# WIZ850io_SCH_V100.net
KiCad netlist of a schematic drawn in Altium Designer
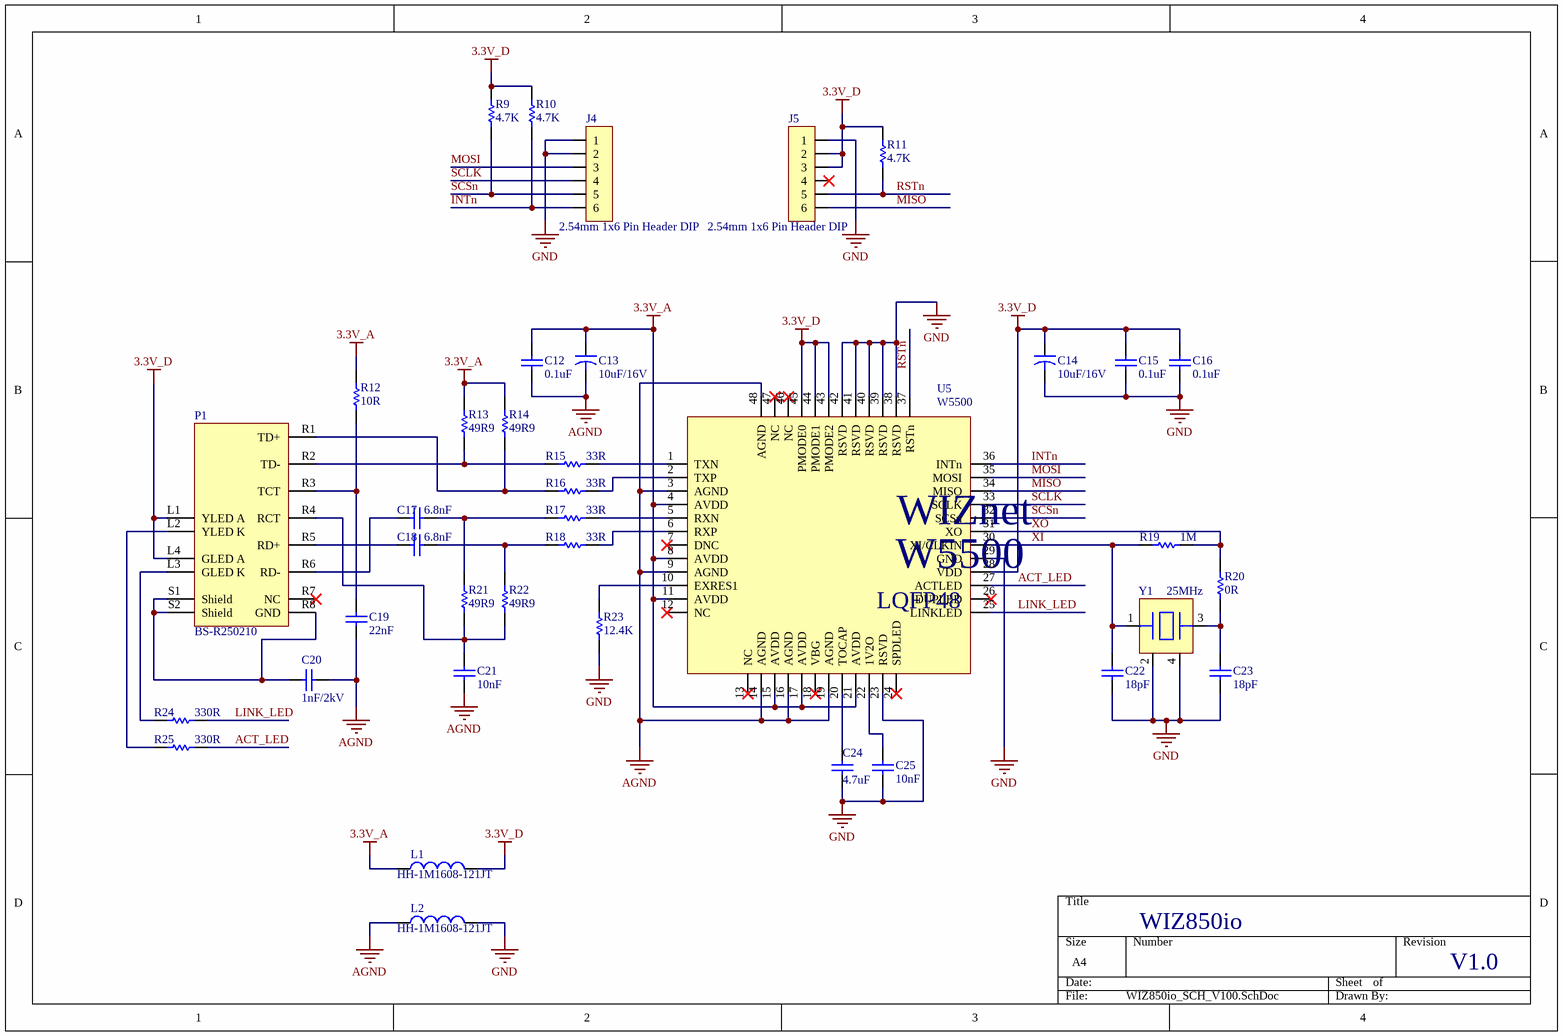
[diagram p0: WIZ850io_SCH_V100.SchDoc]

(export (version "E")
  (design (tool "Eeschema 10.0.6"))
  (components
    (comp (ref "C12")
      (value "0.1uF")
      (footprint "*CAPC1608X90N")
      (description "CAP CER 0.1UF 25V X7R 0603")
      (fields
        (field (name "MANUFACTURER") "Kyocera AVX")
        (field (name "MANUFACTURER PART NUMBER") "06033C104JAT2A")
      )
      (libsource (lib "Scott_lib") (part "CAP-0402"))
    )
    (comp (ref "C13")
      (value "10uF/16V")
      (footprint "10uF 16V")
      (description "Cap Ceramic 10uF 16V X5R 20% SMD 0603 85°C Paper T/R")
      (fields
        (field (name "MANUFACTURER") "Taiyo Yuden")
        (field (name "MANUFACTURER PART NUMBER") "EMK107BBJ106MA-T")
      )
      (libsource (lib "Scott_lib") (part "CAP-A Size"))
    )
    (comp (ref "C14")
      (value "10uF/16V")
      (footprint "10uF 16V")
      (description "Cap Ceramic 10uF 16V X5R 20% SMD 0603 85°C Paper T/R")
      (fields
        (field (name "MANUFACTURER") "Taiyo Yuden")
        (field (name "MANUFACTURER PART NUMBER") "EMK107BBJ106MA-T")
      )
      (libsource (lib "Scott_lib") (part "CAP-A Size"))
    )
    (comp (ref "C15")
      (value "0.1uF")
      (footprint "*CAPC1608X90N")
      (description "CAP CER 0.1UF 25V X7R 0603")
      (fields
        (field (name "MANUFACTURER") "Kyocera AVX")
        (field (name "MANUFACTURER PART NUMBER") "06033C104JAT2A")
      )
      (libsource (lib "Scott_lib") (part "CAP-0402"))
    )
    (comp (ref "C16")
      (value "0.1uF")
      (footprint "*CAPC1608X90N")
      (description "CAP CER 0.1UF 25V X7R 0603")
      (fields
        (field (name "MANUFACTURER") "Kyocera AVX")
        (field (name "MANUFACTURER PART NUMBER") "06033C104JAT2A")
      )
      (libsource (lib "Scott_lib") (part "CAP-0402"))
    )
    (comp (ref "C17")
      (value "6.8nF")
      (footprint "6.8nF")
      (fields
        (field (name "MANUFACTURER") "Kyocera AVX")
        (field (name "MANUFACTURER PART NUMBER") "06031C682KAT2A")
        (field (name "TOLERANCE") "10%")
      )
      (libsource (lib "Scott_lib") (part "CAP-0402"))
    )
    (comp (ref "C18")
      (value "6.8nF")
      (footprint "6.8nF")
      (fields
        (field (name "MANUFACTURER") "Kyocera AVX")
        (field (name "MANUFACTURER PART NUMBER") "06031C682KAT2A")
        (field (name "TOLERANCE") "10%")
      )
      (libsource (lib "Scott_lib") (part "CAP-0402"))
    )
    (comp (ref "C19")
      (value "22nF")
      (footprint "22nF")
      (description "Cap Ceramic 0.022uF 25V X7R 10% SMD 0603 125°C Paper T/R")
      (fields
        (field (name "MANUFACTURER") "Kyocera AVX")
        (field (name "MANUFACTURER PART NUMBER") "06033C223KAT2A")
      )
      (libsource (lib "Scott_lib") (part "CAP-0402"))
    )
    (comp (ref "C20")
      (value "1nF/2kV")
      (footprint "1nF/2kV")
      (description "Cap Ceramic 0.001uF 50V X7R 10% SMD 0603 125C Paper T/R")
      (fields
        (field (name "MANUFACTURER") "Kyocera AVX")
        (field (name "MANUFACTURER PART NUMBER") "06035C102KAT2A")
      )
      (libsource (lib "Scott_lib") (part "CAP-1808"))
    )
    (comp (ref "C21")
      (value "10nF")
      (footprint "10nF")
      (description "0603 10nF 50 V ±10 % Tolerance X7R Surface Mount Multilayer Ceramic Capacitor")
      (fields
        (field (name "MANUFACTURER") "Kyocera AVX")
        (field (name "MANUFACTURER PART NUMBER") "06035C103KAT2A")
      )
      (libsource (lib "Scott_lib") (part "CAP-0402"))
    )
    (comp (ref "C22")
      (value "18pF")
      (footprint "18pF")
      (fields
        (field (name "MANUFACTURER") "Kyocera AVX")
        (field (name "MANUFACTURER PART NUMBER") "06031A180JAT2A")
        (field (name "TOLERANCE") "5%")
      )
      (libsource (lib "Scott_lib") (part "CAP-0402"))
    )
    (comp (ref "C23")
      (value "18pF")
      (footprint "18pF")
      (fields
        (field (name "MANUFACTURER") "Kyocera AVX")
        (field (name "MANUFACTURER PART NUMBER") "06031A180JAT2A")
        (field (name "TOLERANCE") "5%")
      )
      (libsource (lib "Scott_lib") (part "CAP-0402"))
    )
    (comp (ref "C24")
      (value "4.7uF")
      (footprint "4.7 uF")
      (description "Ceramic CAP 0402(1005)")
      (libsource (lib "Scott_lib") (part "CAP-0402"))
    )
    (comp (ref "C25")
      (value "10nF")
      (footprint "10nF")
      (description "0603 10nF 50 V ±10 % Tolerance X7R Surface Mount Multilayer Ceramic Capacitor")
      (fields
        (field (name "MANUFACTURER") "Kyocera AVX")
        (field (name "MANUFACTURER PART NUMBER") "06035C103KAT2A")
      )
      (libsource (lib "Scott_lib") (part "CAP-0805"))
    )
    (comp (ref "J4")
      (value "2.54mm 1x6 Pin Header DIP")
      (footprint "IDC-1X6")
      (libsource (lib "") (part "2.54mm 1x6 Pin Header DIP_1"))
    )
    (comp (ref "J5")
      (value "2.54mm 1x6 Pin Header DIP")
      (footprint "IDC-1X6")
      (libsource (lib "Scott_lib") (part "2.54mm 1x6 Pin Header DIP"))
    )
    (comp (ref "L1")
      (value "HH-1M1608-121JT")
      (footprint "IND-0603")
      (description "Inductor 0603(1608)")
      (libsource (lib "Scott_lib") (part "IND-0603"))
    )
    (comp (ref "L2")
      (value "HH-1M1608-121JT")
      (footprint "IND-0603")
      (description "Inductor 0603(1608)")
      (libsource (lib "Scott_lib") (part "IND-0603"))
    )
    (comp (ref "P1")
      (value "BS-R250210")
      (footprint "BS-R250210")
      (libsource (lib "Scott_lib") (part "BS-R250210"))
    )
    (comp (ref "R9")
      (value "4.7K")
      (footprint "4.7k OHM R")
      (description "SMD Resistor, Thick film 4.7 kOhm,  ±  1 %, 0603, CRCW06034K70FKEA, Vishay")
      (fields
        (field (name "MANUFACTURER") "Vishay Dale")
        (field (name "MANUFACTURER PART NUMBER") "CRA06S0434K70JTA")
      )
      (libsource (lib "Scott_lib") (part "RES-0402"))
    )
    (comp (ref "R10")
      (value "4.7K")
      (footprint "4.7k OHM R")
      (description "SMD Resistor, Thick film 4.7 kOhm,  ±  1 %, 0603, CRCW06034K70FKEA, Vishay")
      (fields
        (field (name "MANUFACTURER") "Vishay Dale")
        (field (name "MANUFACTURER PART NUMBER") "CRA06S0434K70JTA")
      )
      (libsource (lib "Scott_lib") (part "RES-0402"))
    )
    (comp (ref "R11")
      (value "4.7K")
      (footprint "4.7k OHM R")
      (description "SMD Resistor, Thick film 4.7 kOhm,  ±  1 %, 0603, CRCW06034K70FKEA, Vishay")
      (fields
        (field (name "MANUFACTURER") "Vishay")
        (field (name "MANUFACTURER PART NUMBER") "CRCW12064K70FKEA")
      )
      (libsource (lib "Scott_lib") (part "RES-0402"))
    )
    (comp (ref "R12")
      (value "10R")
      (footprint "10OHM R")
      (description "Res Thick Film 0603 10 Ohm 1% 1/10W ±100ppm/°C Molded SMD Paper T/R")
      (fields
        (field (name "MANUFACTURER") "Vishay Dale")
        (field (name "MANUFACTURER PART NUMBER") "CRA06S04310R0JTA")
      )
      (libsource (lib "Scott_lib") (part "RES-0402"))
    )
    (comp (ref "R13")
      (value "49R9")
      (footprint "49R9 OHM")
      (description "VISHAY - TNPW060349R9BEEA. - TNPW0603 49R9 0.1% T-9 ET1 E3 ROHS COMPLIANT: YES")
      (fields
        (field (name "MANUFACTURER") "Vishay Dale")
        (field (name "MANUFACTURER PART NUMBER") "CRA06S04349R9FTA")
      )
      (libsource (lib "Scott_lib") (part "RES-0402"))
    )
    (comp (ref "R14")
      (value "49R9")
      (footprint "49R9 OHM")
      (description "VISHAY - TNPW060349R9BEEA. - TNPW0603 49R9 0.1% T-9 ET1 E3 ROHS COMPLIANT: YES")
      (fields
        (field (name "MANUFACTURER") "Vishay Dale")
        (field (name "MANUFACTURER PART NUMBER") "CRA06S04349R9FTA")
      )
      (libsource (lib "Scott_lib") (part "RES-0402"))
    )
    (comp (ref "R15")
      (value "33R")
      (footprint "33OHM R")
      (fields
        (field (name "MANUFACTURER") "Vishay Dale")
        (field (name "MANUFACTURER PART NUMBER") "CRA06S04333R0JTA")
        (field (name "TOLERANCE") "5%")
      )
      (libsource (lib "Scott_lib") (part "RES-0402"))
    )
    (comp (ref "R16")
      (value "33R")
      (footprint "33OHM R")
      (fields
        (field (name "MANUFACTURER") "Vishay Dale")
        (field (name "MANUFACTURER PART NUMBER") "CRA06S04333R0JTA")
        (field (name "TOLERANCE") "5%")
      )
      (libsource (lib "Scott_lib") (part "RES-0402"))
    )
    (comp (ref "R17")
      (value "33R")
      (footprint "33OHM R")
      (fields
        (field (name "MANUFACTURER") "Vishay Dale")
        (field (name "MANUFACTURER PART NUMBER") "CRA06S04333R0JTA")
        (field (name "TOLERANCE") "5%")
      )
      (libsource (lib "Scott_lib") (part "RES-0402"))
    )
    (comp (ref "R18")
      (value "33R")
      (footprint "33OHM R")
      (fields
        (field (name "MANUFACTURER") "Vishay Dale")
        (field (name "MANUFACTURER PART NUMBER") "CRA06S04333R0JTA")
        (field (name "TOLERANCE") "5%")
      )
      (libsource (lib "Scott_lib") (part "RES-0402"))
    )
    (comp (ref "R19")
      (value "1M")
      (footprint "1M OHM R")
      (description "Thick Film Chip Resistor")
      (fields
        (field (name "MANUFACTURER") "Vishay Dale")
        (field (name "MANUFACTURER PART NUMBER") "CRA06S0431M00JTA")
      )
      (libsource (lib "Scott_lib") (part "RES-0402"))
    )
    (comp (ref "R20")
      (value "0R")
      (footprint "0 OHM R")
      (description "Resistor SMD 0 Ohm 0603 PU=5000 ST, CRCW06030000Z0EA, Vishay")
      (fields
        (field (name "MANUFACTURER") "Vishay")
        (field (name "MANUFACTURER PART NUMBER") "CRCW0603-0000Z0EA")
      )
      (libsource (lib "Scott_lib") (part "RES-0402"))
    )
    (comp (ref "R21")
      (value "49R9")
      (footprint "49R9 OHM")
      (description "VISHAY - TNPW060349R9BEEA. - TNPW0603 49R9 0.1% T-9 ET1 E3 ROHS COMPLIANT: YES")
      (fields
        (field (name "MANUFACTURER") "Vishay Dale")
        (field (name "MANUFACTURER PART NUMBER") "CRA06S04349R9FTA")
      )
      (libsource (lib "Scott_lib") (part "RES-0402"))
    )
    (comp (ref "R22")
      (value "49R9")
      (footprint "49R9 OHM")
      (description "VISHAY - TNPW060349R9BEEA. - TNPW0603 49R9 0.1% T-9 ET1 E3 ROHS COMPLIANT: YES")
      (fields
        (field (name "MANUFACTURER") "Vishay Dale")
        (field (name "MANUFACTURER PART NUMBER") "CRA06S04349R9FTA")
      )
      (libsource (lib "Scott_lib") (part "RES-0402"))
    )
    (comp (ref "R23")
      (value "12.4K")
      (footprint "12.4k OHM R")
      (description "Res Thick Film 0603 12.4K Ohm 1% 1/10W ±100ppm/°C Molded SMD SMD Paper T/R")
      (fields
        (field (name "MANUFACTURER") "Vishay")
        (field (name "MANUFACTURER PART NUMBER") "CRCW0603-12K4FKEA")
      )
      (libsource (lib "Scott_lib") (part "RES-0402"))
    )
    (comp (ref "R24")
      (value "330R")
      (footprint "ahhhh")
      (description "Res Thick Film 0603 330 Ohm 1% 0.1W(1/10W) +/-100ppm/ßC Pad SMD Automotive T/R")
      (fields
        (field (name "MANUFACTURER") "Vishay Dale")
        (field (name "MANUFACTURER PART NUMBER") "CRA06S043330RJTA")
      )
      (libsource (lib "Scott_lib") (part "RES-0402"))
    )
    (comp (ref "R25")
      (value "330R")
      (footprint "ahhhh")
      (description "Res Thick Film 0603 330 Ohm 1% 0.1W(1/10W) +/-100ppm/ßC Pad SMD Automotive T/R")
      (fields
        (field (name "MANUFACTURER") "Vishay Dale")
        (field (name "MANUFACTURER PART NUMBER") "CRA06S043330RJTA")
      )
      (libsource (lib "Scott_lib") (part "RES-0402"))
    )
    (comp (ref "U5")
      (value "W5500")
      (footprint "WIZnet W5500")
      (description "Ethernet CTLR Single Chip 10Mbps/100Mbps 3.3V 48-Pin LQFP Reel")
      (fields (field (name "MANUFACTURER") "WIZnet"))
      (libsource (lib "WIZnet Open-source Hardware Library V1.0") (part "W5500"))
    )
    (comp (ref "Y1")
      (value "25MHz")
      (footprint "OSC-82J0626")
      (description "X-tal 25MHz,3.2x2.5 SMD, CL=18pF")
      (libsource (lib "Scott_lib") (part "OSC-82J0626-25MHz"))
    )
  )
  (nets
    (net (code "1") (name "/ACT_LED") (class "Default")
      (node (ref "R25") (pin "2") (pinfunction "2_2") (pintype "passive"))
      (node (ref "U5") (pin "27") (pinfunction "ACTLED_27") (pintype "passive"))
    )
    (net (code "2") (name "/INTn") (class "Default")
      (node (ref "J4") (pin "6") (pinfunction "6_6") (pintype "passive"))
      (node (ref "R10") (pin "1") (pinfunction "1_1") (pintype "passive"))
      (node (ref "U5") (pin "36") (pinfunction "INTn_36") (pintype "passive"))
    )
    (net (code "3") (name "/LINK_LED") (class "Default")
      (node (ref "R24") (pin "2") (pinfunction "2_2") (pintype "passive"))
      (node (ref "U5") (pin "25") (pinfunction "LINKLED_25") (pintype "passive"))
    )
    (net (code "4") (name "/MISO") (class "Default")
      (node (ref "J5") (pin "6") (pinfunction "6_6") (pintype "passive"))
      (node (ref "U5") (pin "34") (pinfunction "MISO_34") (pintype "passive"))
    )
    (net (code "5") (name "/MOSI") (class "Default")
      (node (ref "J4") (pin "3") (pinfunction "3_3") (pintype "passive"))
      (node (ref "U5") (pin "35") (pinfunction "MOSI_35") (pintype "passive"))
    )
    (net (code "6") (name "/RSTn") (class "Default")
      (node (ref "J5") (pin "5") (pinfunction "5_5") (pintype "passive"))
      (node (ref "R11") (pin "1") (pinfunction "1_1") (pintype "passive"))
      (node (ref "U5") (pin "37") (pinfunction "RSTn_37") (pintype "passive"))
    )
    (net (code "7") (name "/SCLK") (class "Default")
      (node (ref "J4") (pin "4") (pinfunction "4_4") (pintype "passive"))
      (node (ref "U5") (pin "33") (pinfunction "SCLK_33") (pintype "passive"))
    )
    (net (code "8") (name "/SCSn") (class "Default")
      (node (ref "J4") (pin "5") (pinfunction "5_5") (pintype "passive"))
      (node (ref "R9") (pin "1") (pinfunction "1_1") (pintype "passive"))
      (node (ref "U5") (pin "32") (pinfunction "SCSn_32") (pintype "passive"))
    )
    (net (code "9") (name "/XI") (class "Default")
      (node (ref "C22") (pin "2") (pinfunction "2_2") (pintype "passive"))
      (node (ref "R19") (pin "1") (pinfunction "1_1") (pintype "passive"))
      (node (ref "U5") (pin "30") (pinfunction "XI/CLKIN_30") (pintype "passive"))
      (node (ref "Y1") (pin "1") (pinfunction "1_1") (pintype "passive"))
    )
    (net (code "10") (name "/XO") (class "Default")
      (node (ref "R19") (pin "2") (pinfunction "2_2") (pintype "passive"))
      (node (ref "R20") (pin "2") (pinfunction "2_2") (pintype "passive"))
      (node (ref "U5") (pin "31") (pinfunction "XO_31") (pintype "passive"))
    )
    (net (code "11") (name "3.3V_A") (class "Default")
      (node (ref "C12") (pin "2") (pinfunction "2_2") (pintype "passive"))
      (node (ref "C13") (pin "1") (pinfunction "1_1") (pintype "passive"))
      (node (ref "L1") (pin "1") (pinfunction "1_1") (pintype "passive"))
      (node (ref "R12") (pin "2") (pinfunction "2_2") (pintype "passive"))
      (node (ref "R13") (pin "2") (pinfunction "2_2") (pintype "passive"))
      (node (ref "R14") (pin "2") (pinfunction "2_2") (pintype "passive"))
      (node (ref "U5") (pin "11") (pinfunction "AVDD_11") (pintype "passive"))
      (node (ref "U5") (pin "15") (pinfunction "AVDD_15") (pintype "passive"))
      (node (ref "U5") (pin "17") (pinfunction "AVDD_17") (pintype "passive"))
      (node (ref "U5") (pin "21") (pinfunction "AVDD_21") (pintype "passive"))
      (node (ref "U5") (pin "4") (pinfunction "AVDD_4") (pintype "passive"))
      (node (ref "U5") (pin "8") (pinfunction "AVDD_8") (pintype "passive"))
    )
    (net (code "12") (name "3.3V_D") (class "Default")
      (node (ref "C14") (pin "1") (pinfunction "1_1") (pintype "passive"))
      (node (ref "C15") (pin "2") (pinfunction "2_2") (pintype "passive"))
      (node (ref "C16") (pin "2") (pinfunction "2_2") (pintype "passive"))
      (node (ref "J5") (pin "2") (pinfunction "2_2") (pintype "passive"))
      (node (ref "J5") (pin "3") (pinfunction "3_3") (pintype "passive"))
      (node (ref "L1") (pin "2") (pinfunction "2_2") (pintype "passive"))
      (node (ref "P1") (pin "L1") (pinfunction "YLED_A_L1") (pintype "passive"))
      (node (ref "P1") (pin "L4") (pinfunction "GLED_A_L4") (pintype "passive"))
      (node (ref "R10") (pin "2") (pinfunction "2_2") (pintype "passive"))
      (node (ref "R11") (pin "2") (pinfunction "2_2") (pintype "passive"))
      (node (ref "R9") (pin "2") (pinfunction "2_2") (pintype "passive"))
      (node (ref "U5") (pin "28") (pinfunction "VDD_28") (pintype "passive"))
      (node (ref "U5") (pin "43") (pinfunction "PMODE2_43") (pintype "passive"))
      (node (ref "U5") (pin "44") (pinfunction "PMODE1_44") (pintype "passive"))
      (node (ref "U5") (pin "45") (pinfunction "PMODE0_45") (pintype "passive"))
    )
    (net (code "13") (name "AGND") (class "Default")
      (node (ref "C12") (pin "1") (pinfunction "1_1") (pintype "passive"))
      (node (ref "C13") (pin "2") (pinfunction "2_2") (pintype "passive"))
      (node (ref "C19") (pin "1") (pinfunction "1_1") (pintype "passive"))
      (node (ref "C20") (pin "1") (pinfunction "1_1") (pintype "passive"))
      (node (ref "C21") (pin "1") (pinfunction "1_1") (pintype "passive"))
      (node (ref "L2") (pin "1") (pinfunction "1_1") (pintype "passive"))
      (node (ref "U5") (pin "14") (pinfunction "AGND_14") (pintype "passive"))
      (node (ref "U5") (pin "16") (pinfunction "AGND_16") (pintype "passive"))
      (node (ref "U5") (pin "19") (pinfunction "AGND_19") (pintype "passive"))
      (node (ref "U5") (pin "3") (pinfunction "AGND_3") (pintype "passive"))
      (node (ref "U5") (pin "48") (pinfunction "AGND_48") (pintype "passive"))
      (node (ref "U5") (pin "9") (pinfunction "AGND_9") (pintype "passive"))
    )
    (net (code "14") (name "GND") (class "Default")
      (node (ref "C14") (pin "2") (pinfunction "2_2") (pintype "passive"))
      (node (ref "C15") (pin "1") (pinfunction "1_1") (pintype "passive"))
      (node (ref "C16") (pin "1") (pinfunction "1_1") (pintype "passive"))
      (node (ref "C22") (pin "1") (pinfunction "1_1") (pintype "passive"))
      (node (ref "C23") (pin "1") (pinfunction "1_1") (pintype "passive"))
      (node (ref "C24") (pin "1") (pinfunction "1_1") (pintype "passive"))
      (node (ref "C25") (pin "1") (pinfunction "1_1") (pintype "passive"))
      (node (ref "J4") (pin "1") (pinfunction "1_1") (pintype "passive"))
      (node (ref "J4") (pin "2") (pinfunction "2_2") (pintype "passive"))
      (node (ref "J5") (pin "1") (pinfunction "1_1") (pintype "passive"))
      (node (ref "L2") (pin "2") (pinfunction "2_2") (pintype "passive"))
      (node (ref "R23") (pin "1") (pinfunction "1_1") (pintype "passive"))
      (node (ref "U5") (pin "23") (pinfunction "RSVD_23") (pintype "passive"))
      (node (ref "U5") (pin "29") (pinfunction "GND_29") (pintype "passive"))
      (node (ref "U5") (pin "38") (pinfunction "RSVD_38") (pintype "passive"))
      (node (ref "U5") (pin "39") (pinfunction "RSVD_39") (pintype "passive"))
      (node (ref "U5") (pin "40") (pinfunction "RSVD_40") (pintype "passive"))
      (node (ref "U5") (pin "41") (pinfunction "RSVD_41") (pintype "passive"))
      (node (ref "U5") (pin "42") (pinfunction "RSVD_42") (pintype "passive"))
      (node (ref "Y1") (pin "2") (pinfunction "2_2") (pintype "passive"))
      (node (ref "Y1") (pin "4") (pinfunction "4_4") (pintype "passive"))
    )
    (net (code "15") (name "Net-(C17-Pad2)") (class "Default")
      (node (ref "C17") (pin "2") (pinfunction "2_2") (pintype "passive"))
      (node (ref "R17") (pin "1") (pinfunction "1_1") (pintype "passive"))
      (node (ref "R21") (pin "2") (pinfunction "2_2") (pintype "passive"))
    )
    (net (code "16") (name "Net-(C18-Pad2)") (class "Default")
      (node (ref "C18") (pin "2") (pinfunction "2_2") (pintype "passive"))
      (node (ref "R18") (pin "1") (pinfunction "1_1") (pintype "passive"))
      (node (ref "R22") (pin "2") (pinfunction "2_2") (pintype "passive"))
    )
    (net (code "17") (name "Net-(C23-Pad2)") (class "Default")
      (node (ref "C23") (pin "2") (pinfunction "2_2") (pintype "passive"))
      (node (ref "R20") (pin "1") (pinfunction "1_1") (pintype "passive"))
      (node (ref "Y1") (pin "3") (pinfunction "3_3") (pintype "passive"))
    )
    (net (code "18") (name "Net-(P1-GLED_K)") (class "Default")
      (node (ref "P1") (pin "L3") (pinfunction "GLED_K_L3") (pintype "passive"))
      (node (ref "R24") (pin "1") (pinfunction "1_1") (pintype "passive"))
    )
    (net (code "19") (name "Net-(P1-GND)") (class "Default")
      (node (ref "C20") (pin "2") (pinfunction "2_2") (pintype "passive"))
      (node (ref "P1") (pin "R8") (pinfunction "GND_R8") (pintype "passive"))
      (node (ref "P1") (pin "S1") (pinfunction "Shield_S1") (pintype "passive"))
      (node (ref "P1") (pin "S2") (pinfunction "Shield_S2") (pintype "passive"))
    )
    (net (code "20") (name "Net-(P1-RCT)") (class "Default")
      (node (ref "C21") (pin "2") (pinfunction "2_2") (pintype "passive"))
      (node (ref "P1") (pin "R4") (pinfunction "RCT_R4") (pintype "passive"))
      (node (ref "R21") (pin "1") (pinfunction "1_1") (pintype "passive"))
      (node (ref "R22") (pin "1") (pinfunction "1_1") (pintype "passive"))
    )
    (net (code "21") (name "Net-(P1-RD+)") (class "Default")
      (node (ref "C18") (pin "1") (pinfunction "1_1") (pintype "passive"))
      (node (ref "P1") (pin "R5") (pinfunction "RD+_R5") (pintype "passive"))
    )
    (net (code "22") (name "Net-(P1-RD-)") (class "Default")
      (node (ref "C17") (pin "1") (pinfunction "1_1") (pintype "passive"))
      (node (ref "P1") (pin "R6") (pinfunction "RD-_R6") (pintype "passive"))
    )
    (net (code "23") (name "Net-(P1-TCT)") (class "Default")
      (node (ref "C19") (pin "2") (pinfunction "2_2") (pintype "passive"))
      (node (ref "P1") (pin "R3") (pinfunction "TCT_R3") (pintype "passive"))
      (node (ref "R12") (pin "1") (pinfunction "1_1") (pintype "passive"))
    )
    (net (code "24") (name "Net-(P1-TD+)") (class "Default")
      (node (ref "P1") (pin "R1") (pinfunction "TD+_R1") (pintype "passive"))
      (node (ref "R14") (pin "1") (pinfunction "1_1") (pintype "passive"))
      (node (ref "R16") (pin "1") (pinfunction "1_1") (pintype "passive"))
    )
    (net (code "25") (name "Net-(P1-TD-)") (class "Default")
      (node (ref "P1") (pin "R2") (pinfunction "TD-_R2") (pintype "passive"))
      (node (ref "R13") (pin "1") (pinfunction "1_1") (pintype "passive"))
      (node (ref "R15") (pin "1") (pinfunction "1_1") (pintype "passive"))
    )
    (net (code "26") (name "Net-(P1-YLED_K)") (class "Default")
      (node (ref "P1") (pin "L2") (pinfunction "YLED_K_L2") (pintype "passive"))
      (node (ref "R25") (pin "1") (pinfunction "1_1") (pintype "passive"))
    )
    (net (code "27") (name "Net-(U5-1V2O)") (class "Default")
      (node (ref "C25") (pin "2") (pinfunction "2_2") (pintype "passive"))
      (node (ref "U5") (pin "22") (pinfunction "1V2O_22") (pintype "passive"))
    )
    (net (code "28") (name "Net-(U5-EXRES1)") (class "Default")
      (node (ref "R23") (pin "2") (pinfunction "2_2") (pintype "passive"))
      (node (ref "U5") (pin "10") (pinfunction "EXRES1_10") (pintype "passive"))
    )
    (net (code "29") (name "Net-(U5-RXN)") (class "Default")
      (node (ref "R17") (pin "2") (pinfunction "2_2") (pintype "passive"))
      (node (ref "U5") (pin "5") (pinfunction "RXN_5") (pintype "passive"))
    )
    (net (code "30") (name "Net-(U5-RXP)") (class "Default")
      (node (ref "R18") (pin "2") (pinfunction "2_2") (pintype "passive"))
      (node (ref "U5") (pin "6") (pinfunction "RXP_6") (pintype "passive"))
    )
    (net (code "31") (name "Net-(U5-TOCAP)") (class "Default")
      (node (ref "C24") (pin "2") (pinfunction "2_2") (pintype "passive"))
      (node (ref "U5") (pin "20") (pinfunction "TOCAP_20") (pintype "passive"))
    )
    (net (code "32") (name "Net-(U5-TXN)") (class "Default")
      (node (ref "R15") (pin "2") (pinfunction "2_2") (pintype "passive"))
      (node (ref "U5") (pin "1") (pinfunction "TXN_1") (pintype "passive"))
    )
    (net (code "33") (name "Net-(U5-TXP)") (class "Default")
      (node (ref "R16") (pin "2") (pinfunction "2_2") (pintype "passive"))
      (node (ref "U5") (pin "2") (pinfunction "TXP_2") (pintype "passive"))
    )
    (net (code "34") (name "unconnected-(J5-Pad4)") (class "Default")
      (node (ref "J5") (pin "4") (pinfunction "4_4") (pintype "passive+no_connect"))
    )
    (net (code "35") (name "unconnected-(P1-NC-PadR7)") (class "Default")
      (node (ref "P1") (pin "R7") (pinfunction "NC_R7") (pintype "passive+no_connect"))
    )
    (net (code "36") (name "unconnected-(U5-DNC-Pad7)") (class "Default")
      (node (ref "U5") (pin "7") (pinfunction "DNC_7") (pintype "passive+no_connect"))
    )
    (net (code "37") (name "unconnected-(U5-DUPLED-Pad26)") (class "Default")
      (node (ref "U5") (pin "26") (pinfunction "DUPLED_26") (pintype "passive+no_connect"))
    )
    (net (code "38") (name "unconnected-(U5-NC-Pad12)") (class "Default")
      (node (ref "U5") (pin "12") (pinfunction "NC_12") (pintype "passive+no_connect"))
    )
    (net (code "39") (name "unconnected-(U5-NC-Pad13)") (class "Default")
      (node (ref "U5") (pin "13") (pinfunction "NC_13") (pintype "passive+no_connect"))
    )
    (net (code "40") (name "unconnected-(U5-NC-Pad46)") (class "Default")
      (node (ref "U5") (pin "46") (pinfunction "NC_46") (pintype "passive+no_connect"))
    )
    (net (code "41") (name "unconnected-(U5-NC-Pad47)") (class "Default")
      (node (ref "U5") (pin "47") (pinfunction "NC_47") (pintype "passive+no_connect"))
    )
    (net (code "42") (name "unconnected-(U5-SPDLED-Pad24)") (class "Default")
      (node (ref "U5") (pin "24") (pinfunction "SPDLED_24") (pintype "passive+no_connect"))
    )
    (net (code "43") (name "unconnected-(U5-VBG-Pad18)") (class "Default")
      (node (ref "U5") (pin "18") (pinfunction "VBG_18") (pintype "passive+no_connect"))
    )
  )
)
